# Review_PCD_1_6.net
KiCad netlist of a schematic drawn in EAGLE
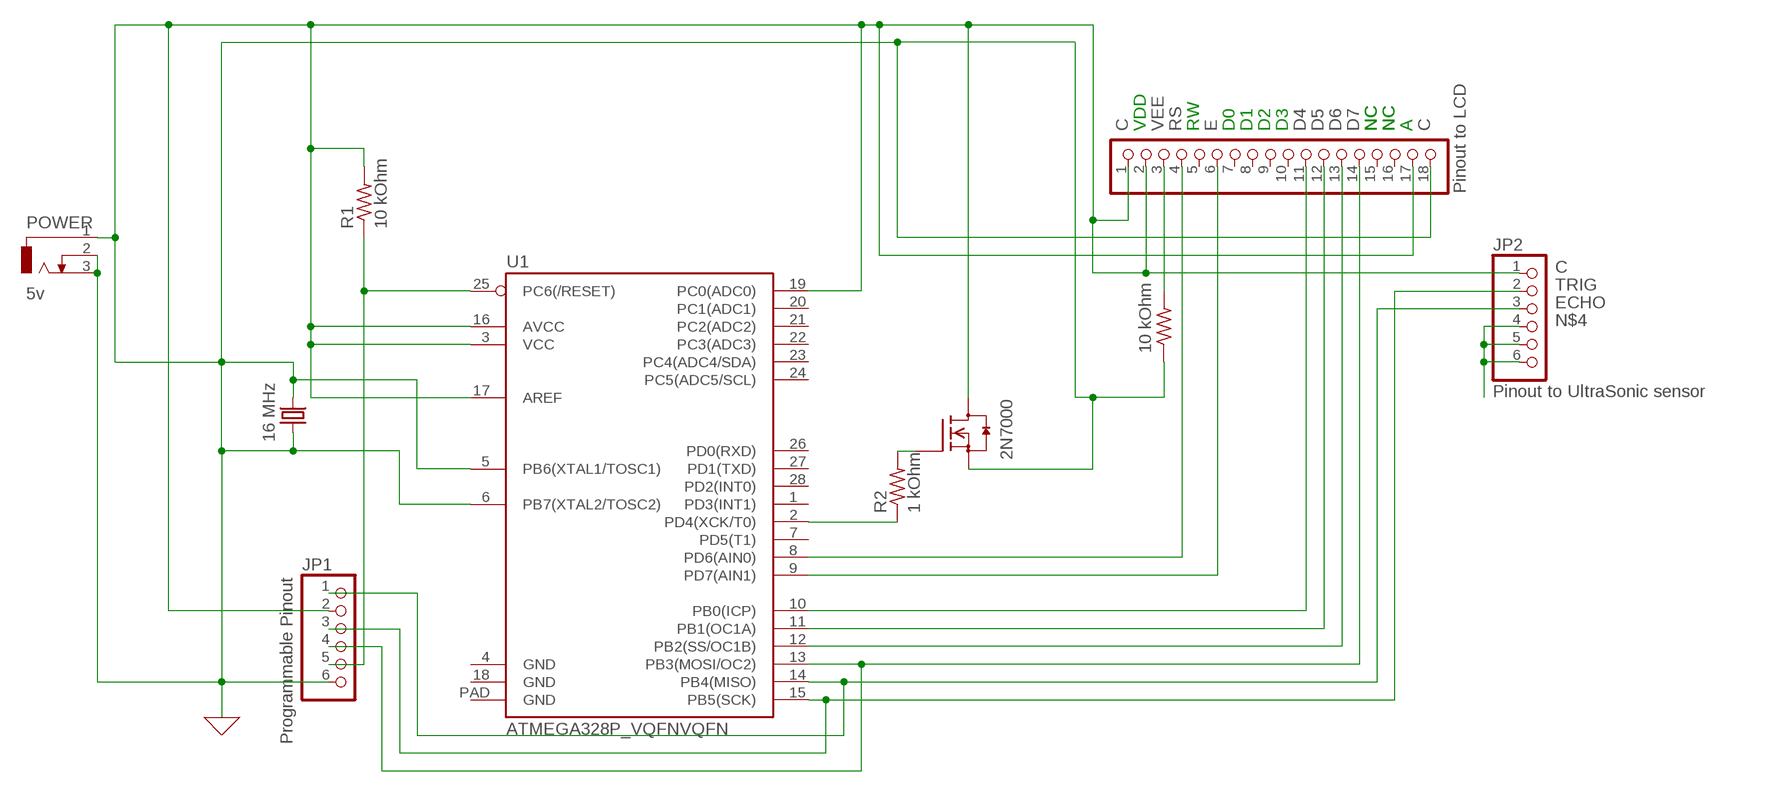
[diagram p0: schematic, sheet 1]

(export (version "E")
  (design (tool "Eeschema 10.0.6"))
  (components
    (comp (ref "JP1")
      (value "Programmable Pinout")
      (footprint "eagle-import:1X06-3.5MM")
      (libsource (lib "eagle-import") (part "PINHD-1X6-3.5MM"))
    )
    (comp (ref "JP2")
      (value "Pinout to UltraSonic sensor")
      (footprint "eagle-import:1X06-BIG")
      (libsource (lib "eagle-import") (part "PINHD-1X6B"))
    )
    (comp (ref "JP3")
      (value "Pinout to LCD")
      (footprint "eagle-import:1X18")
      (libsource (lib "eagle-import") (part "PINHD-1X18"))
    )
    (comp (ref "POWER")
      (value "5v")
      (footprint "eagle-import:DCJ0202")
      (libsource (lib "eagle-import") (part "DCJ0202"))
    )
    (comp (ref "Q1")
      (value "16 MHz")
      (footprint "eagle-import:1.6X1.2")
      (fields (field (name "Q1") "16 MHz"))
      (libsource (lib "eagle-import") (part "KX-4"))
    )
    (comp (ref "Q2")
      (value "2N7000")
      (footprint "eagle-import:TO92")
      (libsource (lib "eagle-import") (part "2N7000KL/BS170KL"))
    )
    (comp (ref "R1")
      (value "10 kOhm")
      (footprint "eagle-import:R2012W")
      (libsource (lib "eagle-import") (part "R-US_R2012W"))
    )
    (comp (ref "R2")
      (value "1 kOhm")
      (footprint "eagle-import:R2012W")
      (fields (field (name "R1") "1 kOhm"))
      (libsource (lib "eagle-import") (part "R-US_R2012W"))
    )
    (comp (ref "R3")
      (value "10 kOhm")
      (footprint "eagle-import:R2012W")
      (fields (field (name "R1") "10 kOhm"))
      (libsource (lib "eagle-import") (part "R-US_R2012W"))
    )
    (comp (ref "U1")
      (value "ATMEGA328P_VQFNVQFN")
      (footprint "eagle-import:VQFN-28")
      (libsource (lib "eagle-import") (part "ATMEGA328P_VQFNVQFN"))
    )
  )
  (nets
    (net (code "1") (name "/D4") (class "Default")
      (node (ref "JP3") (pin "11") (pinfunction "11_11") (pintype "passive"))
      (node (ref "U1") (pin "10") (pinfunction "PB0(ICP)_10") (pintype "bidirectional"))
    )
    (net (code "2") (name "/D5") (class "Default")
      (node (ref "JP3") (pin "12") (pinfunction "12_12") (pintype "passive"))
      (node (ref "U1") (pin "11") (pinfunction "PB1(OC1A)_11") (pintype "bidirectional"))
    )
    (net (code "3") (name "/D6") (class "Default")
      (node (ref "JP3") (pin "13") (pinfunction "13_13") (pintype "passive"))
      (node (ref "U1") (pin "12") (pinfunction "PB2(SS/OC1B)_12") (pintype "bidirectional"))
    )
    (net (code "4") (name "/D7") (class "Default")
      (node (ref "JP1") (pin "4") (pinfunction "4_4") (pintype "passive"))
      (node (ref "JP3") (pin "14") (pinfunction "14_14") (pintype "passive"))
      (node (ref "U1") (pin "13") (pinfunction "PB3(MOSI/OC2)_13") (pintype "bidirectional"))
    )
    (net (code "5") (name "/E") (class "Default")
      (node (ref "JP3") (pin "6") (pinfunction "6_6") (pintype "passive"))
      (node (ref "U1") (pin "9") (pinfunction "PD7(AIN1)_9") (pintype "bidirectional"))
    )
    (net (code "6") (name "/ECHO") (class "Default")
      (node (ref "JP1") (pin "1") (pinfunction "1_1") (pintype "passive"))
      (node (ref "JP2") (pin "3") (pinfunction "3_3") (pintype "passive"))
      (node (ref "U1") (pin "14") (pinfunction "PB4(MISO)_14") (pintype "bidirectional"))
    )
    (net (code "7") (name "/N$4") (class "Default")
      (node (ref "JP2") (pin "4") (pinfunction "4_4") (pintype "passive"))
      (node (ref "JP2") (pin "5") (pinfunction "5_5") (pintype "passive"))
      (node (ref "JP2") (pin "6") (pinfunction "6_6") (pintype "passive"))
    )
    (net (code "8") (name "/RS") (class "Default")
      (node (ref "JP3") (pin "4") (pinfunction "4_4") (pintype "passive"))
      (node (ref "U1") (pin "8") (pinfunction "PD6(AIN0)_8") (pintype "bidirectional"))
    )
    (net (code "9") (name "/TRIG") (class "Default")
      (node (ref "JP1") (pin "3") (pinfunction "3_3") (pintype "passive"))
      (node (ref "JP2") (pin "2") (pinfunction "2_2") (pintype "passive"))
      (node (ref "U1") (pin "15") (pinfunction "PB5(SCK)_15") (pintype "bidirectional"))
    )
    (net (code "10") (name "/VEE") (class "Default")
      (node (ref "JP3") (pin "3") (pinfunction "3_3") (pintype "passive"))
      (node (ref "R3") (pin "2") (pinfunction "2_2") (pintype "passive"))
    )
    (net (code "11") (name "GND") (class "Default")
      (node (ref "JP1") (pin "2") (pinfunction "2_2") (pintype "passive"))
      (node (ref "JP1") (pin "6") (pinfunction "6_6") (pintype "passive"))
      (node (ref "JP2") (pin "1") (pinfunction "1_1") (pintype "passive"))
      (node (ref "JP3") (pin "1") (pinfunction "1_1") (pintype "passive"))
      (node (ref "JP3") (pin "17") (pinfunction "17_17") (pintype "passive"))
      (node (ref "JP3") (pin "18") (pinfunction "18_18") (pintype "passive"))
      (node (ref "JP3") (pin "2") (pinfunction "2_2") (pintype "passive"))
      (node (ref "POWER") (pin "1") (pinfunction "1_1") (pintype "passive"))
      (node (ref "POWER") (pin "2") (pinfunction "2_2") (pintype "passive"))
      (node (ref "POWER") (pin "3") (pinfunction "3_3") (pintype "passive"))
      (node (ref "Q1") (pin "1") (pinfunction "1_1") (pintype "passive"))
      (node (ref "Q1") (pin "3") (pinfunction "2_3") (pintype "passive"))
      (node (ref "Q2") (pin "1") (pinfunction "S_1") (pintype "passive"))
      (node (ref "Q2") (pin "3") (pinfunction "D_3") (pintype "passive"))
      (node (ref "R1") (pin "2") (pinfunction "2_2") (pintype "passive"))
      (node (ref "R3") (pin "1") (pinfunction "1_1") (pintype "passive"))
      (node (ref "U1") (pin "16") (pinfunction "AVCC_16") (pintype "bidirectional"))
      (node (ref "U1") (pin "17") (pinfunction "AREF_17") (pintype "bidirectional"))
      (node (ref "U1") (pin "19") (pinfunction "PC0(ADC0)_19") (pintype "bidirectional"))
      (node (ref "U1") (pin "3") (pinfunction "VCC_3") (pintype "bidirectional"))
      (node (ref "U1") (pin "5") (pinfunction "PB6(XTAL1/TOSC1)_5") (pintype "bidirectional"))
      (node (ref "U1") (pin "6") (pinfunction "PB7(XTAL2/TOSC2)_6") (pintype "bidirectional"))
    )
    (net (code "12") (name "Net-(Q2-G)") (class "Default")
      (node (ref "Q2") (pin "2") (pinfunction "G_2") (pintype "passive"))
      (node (ref "R2") (pin "2") (pinfunction "2_2") (pintype "passive"))
    )
    (net (code "13") (name "Net-(U1-PC6({slash}RESET))") (class "Default")
      (node (ref "JP1") (pin "5") (pinfunction "5_5") (pintype "passive"))
      (node (ref "R1") (pin "1") (pinfunction "1_1") (pintype "passive"))
      (node (ref "U1") (pin "25") (pinfunction "PC6(/RESET)_25") (pintype "bidirectional"))
    )
    (net (code "14") (name "Net-(U1-PD4(XCK{slash}T0))") (class "Default")
      (node (ref "R2") (pin "1") (pinfunction "1_1") (pintype "passive"))
      (node (ref "U1") (pin "2") (pinfunction "PD4(XCK/T0)_2") (pintype "bidirectional"))
    )
    (net (code "15") (name "unconnected-(JP3-Pad5)") (class "Default")
      (node (ref "JP3") (pin "5") (pinfunction "5_5") (pintype "passive"))
    )
    (net (code "16") (name "unconnected-(JP3-Pad7)") (class "Default")
      (node (ref "JP3") (pin "7") (pinfunction "7_7") (pintype "passive"))
    )
    (net (code "17") (name "unconnected-(JP3-Pad8)") (class "Default")
      (node (ref "JP3") (pin "8") (pinfunction "8_8") (pintype "passive"))
    )
    (net (code "18") (name "unconnected-(JP3-Pad9)") (class "Default")
      (node (ref "JP3") (pin "9") (pinfunction "9_9") (pintype "passive"))
    )
    (net (code "19") (name "unconnected-(JP3-Pad10)") (class "Default")
      (node (ref "JP3") (pin "10") (pinfunction "10_10") (pintype "passive"))
    )
    (net (code "20") (name "unconnected-(JP3-Pad15)") (class "Default")
      (node (ref "JP3") (pin "15") (pinfunction "15_15") (pintype "passive"))
    )
    (net (code "21") (name "unconnected-(JP3-Pad16)") (class "Default")
      (node (ref "JP3") (pin "16") (pinfunction "16_16") (pintype "passive"))
    )
    (net (code "22") (name "unconnected-(U1-GND-Pad4)") (class "Default")
      (node (ref "U1") (pin "4") (pinfunction "GND_4") (pintype "bidirectional"))
    )
    (net (code "23") (name "unconnected-(U1-GND-Pad18)") (class "Default")
      (node (ref "U1") (pin "18") (pinfunction "GND_18") (pintype "bidirectional"))
    )
    (net (code "24") (name "unconnected-(U1-GND-PadPAD)") (class "Default")
      (node (ref "U1") (pin "PAD") (pinfunction "GND_PAD") (pintype "bidirectional"))
    )
    (net (code "25") (name "unconnected-(U1-PC1(ADC1)-Pad20)") (class "Default")
      (node (ref "U1") (pin "20") (pinfunction "PC1(ADC1)_20") (pintype "bidirectional"))
    )
    (net (code "26") (name "unconnected-(U1-PC2(ADC2)-Pad21)") (class "Default")
      (node (ref "U1") (pin "21") (pinfunction "PC2(ADC2)_21") (pintype "bidirectional"))
    )
    (net (code "27") (name "unconnected-(U1-PC3(ADC3)-Pad22)") (class "Default")
      (node (ref "U1") (pin "22") (pinfunction "PC3(ADC3)_22") (pintype "bidirectional"))
    )
    (net (code "28") (name "unconnected-(U1-PC4(ADC4{slash}SDA)-Pad23)") (class "Default")
      (node (ref "U1") (pin "23") (pinfunction "PC4(ADC4/SDA)_23") (pintype "bidirectional"))
    )
    (net (code "29") (name "unconnected-(U1-PC5(ADC5{slash}SCL)-Pad24)") (class "Default")
      (node (ref "U1") (pin "24") (pinfunction "PC5(ADC5/SCL)_24") (pintype "bidirectional"))
    )
    (net (code "30") (name "unconnected-(U1-PD0(RXD)-Pad26)") (class "Default")
      (node (ref "U1") (pin "26") (pinfunction "PD0(RXD)_26") (pintype "bidirectional"))
    )
    (net (code "31") (name "unconnected-(U1-PD1(TXD)-Pad27)") (class "Default")
      (node (ref "U1") (pin "27") (pinfunction "PD1(TXD)_27") (pintype "bidirectional"))
    )
    (net (code "32") (name "unconnected-(U1-PD2(INT0)-Pad28)") (class "Default")
      (node (ref "U1") (pin "28") (pinfunction "PD2(INT0)_28") (pintype "bidirectional"))
    )
    (net (code "33") (name "unconnected-(U1-PD3(INT1)-Pad1)") (class "Default")
      (node (ref "U1") (pin "1") (pinfunction "PD3(INT1)_1") (pintype "bidirectional"))
    )
    (net (code "34") (name "unconnected-(U1-PD5(T1)-Pad7)") (class "Default")
      (node (ref "U1") (pin "7") (pinfunction "PD5(T1)_7") (pintype "bidirectional"))
    )
  )
)
